# SHIFTER.net
KiCad netlist of a schematic drawn in EAGLE
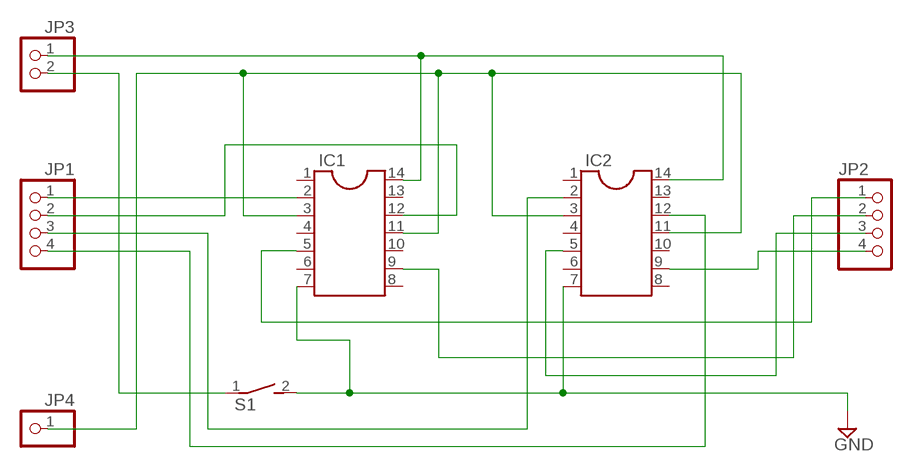
[diagram p0: schematic, sheet 1]

(export (version "E")
  (design (tool "Eeschema 10.0.6"))
  (components
    (comp (ref "IC1")
      (value "DIL14")
      (footprint "eagle-import:DIL14")
      (libsource (lib "eagle-import") (part "DIL14"))
    )
    (comp (ref "IC2")
      (value "DIL14")
      (footprint "eagle-import:DIL14")
      (libsource (lib "eagle-import") (part "DIL14"))
    )
    (comp (ref "JP1")
      (value "PINHD-1X4")
      (footprint "eagle-import:1X04")
      (libsource (lib "eagle-import") (part "PINHD-1X4"))
    )
    (comp (ref "JP2")
      (value "PINHD-1X4")
      (footprint "eagle-import:1X04")
      (libsource (lib "eagle-import") (part "PINHD-1X4"))
    )
    (comp (ref "JP3")
      (value "PINHD-1X2")
      (footprint "eagle-import:1X02")
      (libsource (lib "eagle-import") (part "PINHD-1X2"))
    )
    (comp (ref "JP4")
      (value "PINHD-1X1")
      (footprint "eagle-import:1X01")
      (libsource (lib "eagle-import") (part "PINHD-1X1"))
    )
    (comp (ref "S1")
      (value "DS01E")
      (footprint "eagle-import:DS-01")
      (libsource (lib "eagle-import") (part "DS01E"))
    )
  )
  (nets
    (net (code "1") (name "GND") (class "Default")
      (node (ref "IC1") (pin "7") (pinfunction "7_7") (pintype "passive"))
      (node (ref "IC2") (pin "7") (pinfunction "7_7") (pintype "passive"))
      (node (ref "S1") (pin "2") (pinfunction "2_2") (pintype "passive"))
    )
    (net (code "2") (name "Net-(IC1-Pad2)") (class "Default")
      (node (ref "IC1") (pin "2") (pinfunction "2_2") (pintype "passive"))
      (node (ref "JP1") (pin "1") (pinfunction "1_1") (pintype "passive"))
    )
    (net (code "3") (name "Net-(IC1-Pad5)") (class "Default")
      (node (ref "IC1") (pin "5") (pinfunction "5_5") (pintype "passive"))
      (node (ref "JP2") (pin "1") (pinfunction "1_1") (pintype "passive"))
    )
    (net (code "4") (name "Net-(IC1-Pad9)") (class "Default")
      (node (ref "IC1") (pin "9") (pinfunction "9_9") (pintype "passive"))
      (node (ref "JP2") (pin "2") (pinfunction "2_2") (pintype "passive"))
    )
    (net (code "5") (name "Net-(IC1-Pad11)") (class "Default")
      (node (ref "IC1") (pin "11") (pinfunction "11_11") (pintype "passive"))
      (node (ref "IC1") (pin "3") (pinfunction "3_3") (pintype "passive"))
      (node (ref "IC2") (pin "11") (pinfunction "11_11") (pintype "passive"))
      (node (ref "IC2") (pin "3") (pinfunction "3_3") (pintype "passive"))
      (node (ref "JP4") (pin "1") (pinfunction "1_1") (pintype "passive"))
    )
    (net (code "6") (name "Net-(IC1-Pad12)") (class "Default")
      (node (ref "IC1") (pin "12") (pinfunction "12_12") (pintype "passive"))
      (node (ref "JP1") (pin "2") (pinfunction "2_2") (pintype "passive"))
    )
    (net (code "7") (name "Net-(IC1-Pad14)") (class "Default")
      (node (ref "IC1") (pin "14") (pinfunction "14_14") (pintype "passive"))
      (node (ref "IC2") (pin "14") (pinfunction "14_14") (pintype "passive"))
      (node (ref "JP3") (pin "1") (pinfunction "1_1") (pintype "passive"))
    )
    (net (code "8") (name "Net-(IC2-Pad2)") (class "Default")
      (node (ref "IC2") (pin "2") (pinfunction "2_2") (pintype "passive"))
      (node (ref "JP1") (pin "3") (pinfunction "3_3") (pintype "passive"))
    )
    (net (code "9") (name "Net-(IC2-Pad5)") (class "Default")
      (node (ref "IC2") (pin "5") (pinfunction "5_5") (pintype "passive"))
      (node (ref "JP2") (pin "3") (pinfunction "3_3") (pintype "passive"))
    )
    (net (code "10") (name "Net-(IC2-Pad9)") (class "Default")
      (node (ref "IC2") (pin "9") (pinfunction "9_9") (pintype "passive"))
      (node (ref "JP2") (pin "4") (pinfunction "4_4") (pintype "passive"))
    )
    (net (code "11") (name "Net-(IC2-Pad12)") (class "Default")
      (node (ref "IC2") (pin "12") (pinfunction "12_12") (pintype "passive"))
      (node (ref "JP1") (pin "4") (pinfunction "4_4") (pintype "passive"))
    )
    (net (code "12") (name "Net-(JP3-Pad2)") (class "Default")
      (node (ref "JP3") (pin "2") (pinfunction "2_2") (pintype "passive"))
      (node (ref "S1") (pin "1") (pinfunction "1_1") (pintype "passive"))
    )
    (net (code "13") (name "unconnected-(IC1-Pad1)") (class "Default")
      (node (ref "IC1") (pin "1") (pinfunction "1_1") (pintype "passive"))
    )
    (net (code "14") (name "unconnected-(IC1-Pad4)") (class "Default")
      (node (ref "IC1") (pin "4") (pinfunction "4_4") (pintype "passive"))
    )
    (net (code "15") (name "unconnected-(IC1-Pad6)") (class "Default")
      (node (ref "IC1") (pin "6") (pinfunction "6_6") (pintype "passive"))
    )
    (net (code "16") (name "unconnected-(IC1-Pad8)") (class "Default")
      (node (ref "IC1") (pin "8") (pinfunction "8_8") (pintype "passive"))
    )
    (net (code "17") (name "unconnected-(IC1-Pad10)") (class "Default")
      (node (ref "IC1") (pin "10") (pinfunction "10_10") (pintype "passive"))
    )
    (net (code "18") (name "unconnected-(IC1-Pad13)") (class "Default")
      (node (ref "IC1") (pin "13") (pinfunction "13_13") (pintype "passive"))
    )
    (net (code "19") (name "unconnected-(IC2-Pad1)") (class "Default")
      (node (ref "IC2") (pin "1") (pinfunction "1_1") (pintype "passive"))
    )
    (net (code "20") (name "unconnected-(IC2-Pad4)") (class "Default")
      (node (ref "IC2") (pin "4") (pinfunction "4_4") (pintype "passive"))
    )
    (net (code "21") (name "unconnected-(IC2-Pad6)") (class "Default")
      (node (ref "IC2") (pin "6") (pinfunction "6_6") (pintype "passive"))
    )
    (net (code "22") (name "unconnected-(IC2-Pad8)") (class "Default")
      (node (ref "IC2") (pin "8") (pinfunction "8_8") (pintype "passive"))
    )
    (net (code "23") (name "unconnected-(IC2-Pad10)") (class "Default")
      (node (ref "IC2") (pin "10") (pinfunction "10_10") (pintype "passive"))
    )
    (net (code "24") (name "unconnected-(IC2-Pad13)") (class "Default")
      (node (ref "IC2") (pin "13") (pinfunction "13_13") (pintype "passive"))
    )
  )
)
